# Sheet1.net
KiCad netlist of a schematic drawn in Altium Designer
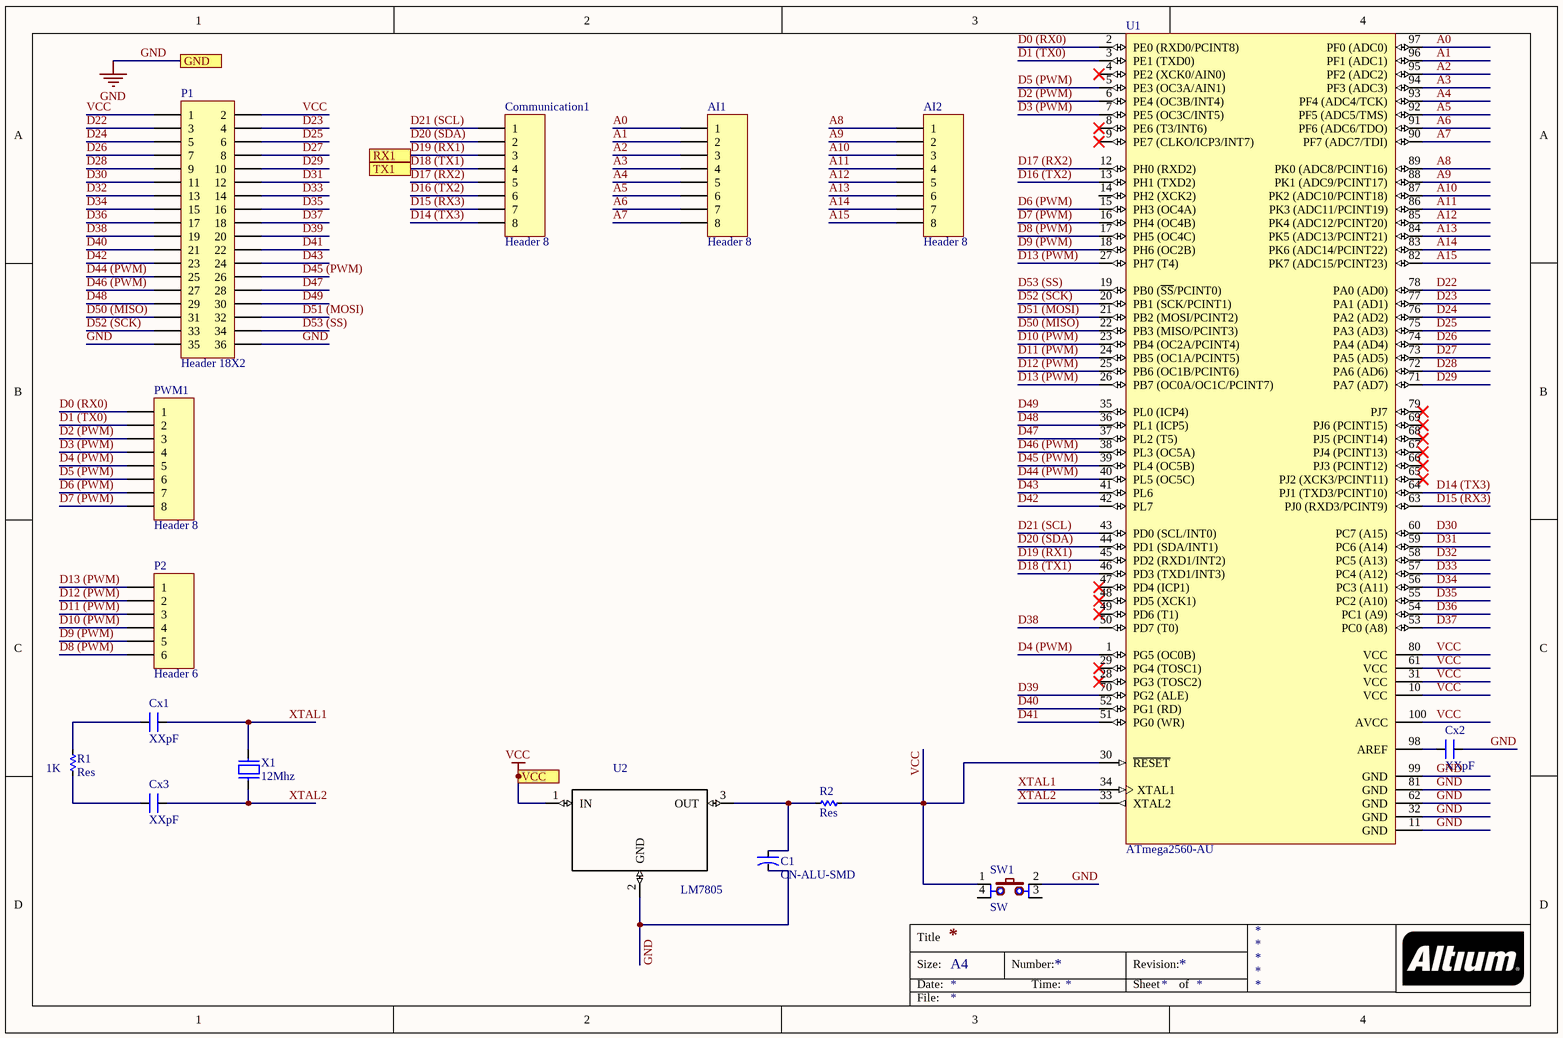
[diagram p0: Sheet1.SchDoc]

(export (version "E")
  (design (tool "Eeschema 10.0.6"))
  (components
    (comp (ref "AI1")
      (value "Header 8")
      (footprint "HDR1X8")
      (description "Header, 8-Pin")
      (fields (field (name "PUBLISHER") "Altium Limited"))
      (libsource (lib "Miscellaneous Connectors") (part "Header 8"))
    )
    (comp (ref "AI2")
      (value "Header 8")
      (footprint "HDR1X8")
      (description "Header, 8-Pin")
      (fields (field (name "PUBLISHER") "Altium Limited"))
      (libsource (lib "Miscellaneous Connectors") (part "Header 8"))
    )
    (comp (ref "C1")
      (value "CN-ALU-SMD")
      (footprint "CAP-ALU-SMD-4.5x5x1.4")
      (description "Polarized Capacitor (Axial)")
      (fields (field (name "PUBLISHER") "Altium Limited"))
      (libsource (lib "LIBRARY_altium mulinhkien") (part "CN-ALU-SMD"))
    )
    (comp (ref "Communication1")
      (value "Header 8")
      (footprint "HDR1X8")
      (description "Header, 8-Pin")
      (fields (field (name "PUBLISHER") "Altium Limited"))
      (libsource (lib "Miscellaneous Connectors") (part "Header 8"))
    )
    (comp (ref "Cx1")
      (value "XXpF")
      (footprint "CN-SMD-1206")
      (libsource (lib "LIBRARY_altium mulinhkien") (part "CN"))
    )
    (comp (ref "Cx2")
      (value "XXpF")
      (footprint "CN-SMD-1206")
      (libsource (lib "LIBRARY_altium mulinhkien") (part "CN"))
    )
    (comp (ref "Cx3")
      (value "XXpF")
      (footprint "CN-SMD-1206")
      (libsource (lib "LIBRARY_altium mulinhkien") (part "CN"))
    )
    (comp (ref "P1")
      (value "Header 18X2")
      (footprint "HDR2X18")
      (description "Header, 18-Pin, Dual row")
      (fields (field (name "PUBLISHER") "Altium Limited"))
      (libsource (lib "Miscellaneous Connectors") (part "Header 18X2"))
    )
    (comp (ref "P2")
      (value "Header 6")
      (footprint "HDR1X6")
      (description "Header, 6-Pin")
      (fields (field (name "PUBLISHER") "Altium Limited"))
      (libsource (lib "Miscellaneous Connectors") (part "Header 6"))
    )
    (comp (ref "PWM1")
      (value "Header 8")
      (footprint "HDR1X8")
      (description "Header, 8-Pin")
      (fields (field (name "PUBLISHER") "Altium Limited"))
      (libsource (lib "Miscellaneous Connectors") (part "Header 8"))
    )
    (comp (ref "R1")
      (value "Res")
      (footprint "RES-SMD-1206")
      (description "Resistor")
      (fields
        (field (name "MANUFACTURER") "Generic Components")
        (field (name "ALTIUM_VALUE") "1K")
        (field (name "PUBLISHER") "Altium Hobart Technology Centre")
      )
      (libsource (lib "LIBRARY_altium mulinhkien") (part "Res-SMD"))
    )
    (comp (ref "R2")
      (value "Res")
      (footprint "RES-SMD-1206")
      (description "Resistor")
      (fields
        (field (name "MANUFACTURER") "Generic Components")
        (field (name "PUBLISHER") "Altium Hobart Technology Centre")
      )
      (libsource (lib "LIBRARY_altium mulinhkien") (part "Res-SMD"))
    )
    (comp (ref "SW1")
      (value "SW")
      (footprint "SW2-DIP")
      (description "Switch button 4 pin")
      (libsource (lib "LIBRARY_altium mulinhkien") (part "SW4"))
    )
    (comp (ref "U1")
      (value "ATmega2560-AU")
      (footprint "TQFP100L")
      (libsource (lib "LIBRARY_altium mulinhkien") (part "ATmega2560-AU"))
    )
    (comp (ref "U2")
      (value "LM7805")
      (footprint "*TO220")
      (fields (field (name "MF") "Texas Instruments"))
      (libsource (lib "LM7805") (part "LM7805"))
    )
    (comp (ref "X1")
      (value "12Mhz")
      (footprint "XT2")
      (description "Crystal, 32.768 KHz, -40 to 85 degC, 3.2 x 1.5 x 0.9 mm SMD")
      (libsource (lib "LIBRARY_altium mulinhkien") (part "XT2"))
    )
  )
  (nets
    (net (code "1") (name "/A0") (class "Default")
      (node (ref "AI1") (pin "1") (pinfunction "1_1") (pintype "passive"))
      (node (ref "U1") (pin "97") (pinfunction "PF0_(ADC0)_97") (pintype "bidirectional"))
    )
    (net (code "2") (name "/A1") (class "Default")
      (node (ref "AI1") (pin "2") (pinfunction "2_2") (pintype "passive"))
      (node (ref "U1") (pin "96") (pinfunction "PF1_(ADC1)_96") (pintype "bidirectional"))
    )
    (net (code "3") (name "/A2") (class "Default")
      (node (ref "AI1") (pin "3") (pinfunction "3_3") (pintype "passive"))
      (node (ref "U1") (pin "95") (pinfunction "PF2_(ADC2)_95") (pintype "bidirectional"))
    )
    (net (code "4") (name "/A3") (class "Default")
      (node (ref "AI1") (pin "4") (pinfunction "4_4") (pintype "passive"))
      (node (ref "U1") (pin "94") (pinfunction "PF3_(ADC3)_94") (pintype "bidirectional"))
    )
    (net (code "5") (name "/A4") (class "Default")
      (node (ref "AI1") (pin "5") (pinfunction "5_5") (pintype "passive"))
      (node (ref "U1") (pin "93") (pinfunction "PF4_(ADC4/TCK)_93") (pintype "bidirectional"))
    )
    (net (code "6") (name "/A5") (class "Default")
      (node (ref "AI1") (pin "6") (pinfunction "6_6") (pintype "passive"))
      (node (ref "U1") (pin "92") (pinfunction "PF5_(ADC5/TMS)_92") (pintype "bidirectional"))
    )
    (net (code "7") (name "/A6") (class "Default")
      (node (ref "AI1") (pin "7") (pinfunction "7_7") (pintype "passive"))
      (node (ref "U1") (pin "91") (pinfunction "PF6_(ADC6/TDO)_91") (pintype "bidirectional"))
    )
    (net (code "8") (name "/A7") (class "Default")
      (node (ref "AI1") (pin "8") (pinfunction "8_8") (pintype "passive"))
      (node (ref "U1") (pin "90") (pinfunction "PF7_(ADC7/TDI)_90") (pintype "bidirectional"))
    )
    (net (code "9") (name "/A8") (class "Default")
      (node (ref "AI2") (pin "1") (pinfunction "1_1") (pintype "passive"))
      (node (ref "U1") (pin "89") (pinfunction "PK0_(ADC8/PCINT16)_89") (pintype "bidirectional"))
    )
    (net (code "10") (name "/A9") (class "Default")
      (node (ref "AI2") (pin "2") (pinfunction "2_2") (pintype "passive"))
      (node (ref "U1") (pin "88") (pinfunction "PK1_(ADC9/PCINT17)_88") (pintype "bidirectional"))
    )
    (net (code "11") (name "/A10") (class "Default")
      (node (ref "AI2") (pin "3") (pinfunction "3_3") (pintype "passive"))
      (node (ref "U1") (pin "87") (pinfunction "PK2_(ADC10/PCINT18)_87") (pintype "bidirectional"))
    )
    (net (code "12") (name "/A11") (class "Default")
      (node (ref "AI2") (pin "4") (pinfunction "4_4") (pintype "passive"))
      (node (ref "U1") (pin "86") (pinfunction "PK3_(ADC11/PCINT19)_86") (pintype "bidirectional"))
    )
    (net (code "13") (name "/A12") (class "Default")
      (node (ref "AI2") (pin "5") (pinfunction "5_5") (pintype "passive"))
      (node (ref "U1") (pin "85") (pinfunction "PK4_(ADC12/PCINT20)_85") (pintype "bidirectional"))
    )
    (net (code "14") (name "/A13") (class "Default")
      (node (ref "AI2") (pin "6") (pinfunction "6_6") (pintype "passive"))
      (node (ref "U1") (pin "84") (pinfunction "PK5_(ADC13/PCINT21)_84") (pintype "bidirectional"))
    )
    (net (code "15") (name "/A14") (class "Default")
      (node (ref "AI2") (pin "7") (pinfunction "7_7") (pintype "passive"))
      (node (ref "U1") (pin "83") (pinfunction "PK6_(ADC14/PCINT22)_83") (pintype "bidirectional"))
    )
    (net (code "16") (name "/A15") (class "Default")
      (node (ref "AI2") (pin "8") (pinfunction "8_8") (pintype "passive"))
      (node (ref "U1") (pin "82") (pinfunction "PK7_(ADC15/PCINT23)_82") (pintype "bidirectional"))
    )
    (net (code "17") (name "/D0 (RX0)") (class "Default")
      (node (ref "PWM1") (pin "1") (pinfunction "1_1") (pintype "passive"))
      (node (ref "U1") (pin "2") (pinfunction "PE0_(RXD0/PCINT8)_2") (pintype "bidirectional"))
    )
    (net (code "18") (name "/D1 (TX0)") (class "Default")
      (node (ref "PWM1") (pin "2") (pinfunction "2_2") (pintype "passive"))
      (node (ref "U1") (pin "3") (pinfunction "PE1_(TXD0)_3") (pintype "bidirectional"))
    )
    (net (code "19") (name "/D2 (PWM)") (class "Default")
      (node (ref "PWM1") (pin "3") (pinfunction "3_3") (pintype "passive"))
      (node (ref "U1") (pin "6") (pinfunction "PE4_(OC3B/INT4)_6") (pintype "bidirectional"))
    )
    (net (code "20") (name "/D3 (PWM)") (class "Default")
      (node (ref "PWM1") (pin "4") (pinfunction "4_4") (pintype "passive"))
      (node (ref "U1") (pin "7") (pinfunction "PE5_(OC3C/INT5)_7") (pintype "bidirectional"))
    )
    (net (code "21") (name "/D4 (PWM)") (class "Default")
      (node (ref "PWM1") (pin "5") (pinfunction "5_5") (pintype "passive"))
      (node (ref "U1") (pin "1") (pinfunction "PG5_(OC0B)_1") (pintype "bidirectional"))
    )
    (net (code "22") (name "/D5 (PWM)") (class "Default")
      (node (ref "PWM1") (pin "6") (pinfunction "6_6") (pintype "passive"))
      (node (ref "U1") (pin "5") (pinfunction "PE3_(OC3A/AIN1)_5") (pintype "bidirectional"))
    )
    (net (code "23") (name "/D6 (PWM)") (class "Default")
      (node (ref "PWM1") (pin "7") (pinfunction "7_7") (pintype "passive"))
      (node (ref "U1") (pin "15") (pinfunction "PH3_(OC4A)_15") (pintype "bidirectional"))
    )
    (net (code "24") (name "/D7 (PWM)") (class "Default")
      (node (ref "PWM1") (pin "8") (pinfunction "8_8") (pintype "passive"))
      (node (ref "U1") (pin "16") (pinfunction "PH4_(OC4B)_16") (pintype "bidirectional"))
    )
    (net (code "25") (name "/D8 (PWM)") (class "Default")
      (node (ref "P2") (pin "6") (pinfunction "6_6") (pintype "passive"))
      (node (ref "U1") (pin "17") (pinfunction "PH5_(OC4C)_17") (pintype "bidirectional"))
    )
    (net (code "26") (name "/D9 (PWM)") (class "Default")
      (node (ref "P2") (pin "5") (pinfunction "5_5") (pintype "passive"))
      (node (ref "U1") (pin "18") (pinfunction "PH6_(OC2B)_18") (pintype "bidirectional"))
    )
    (net (code "27") (name "/D10 (PWM)") (class "Default")
      (node (ref "P2") (pin "4") (pinfunction "4_4") (pintype "passive"))
      (node (ref "U1") (pin "23") (pinfunction "PB4_(OC2A/PCINT4)_23") (pintype "bidirectional"))
    )
    (net (code "28") (name "/D11 (PWM)") (class "Default")
      (node (ref "P2") (pin "3") (pinfunction "3_3") (pintype "passive"))
      (node (ref "U1") (pin "24") (pinfunction "PB5_(OC1A/PCINT5)_24") (pintype "bidirectional"))
    )
    (net (code "29") (name "/D12 (PWM)") (class "Default")
      (node (ref "P2") (pin "2") (pinfunction "2_2") (pintype "passive"))
      (node (ref "U1") (pin "25") (pinfunction "PB6_(OC1B/PCINT6)_25") (pintype "bidirectional"))
    )
    (net (code "30") (name "/D13 (PWM)") (class "Default")
      (node (ref "P2") (pin "1") (pinfunction "1_1") (pintype "passive"))
      (node (ref "U1") (pin "26") (pinfunction "PB7_(OC0A/OC1C/PCINT7)_26") (pintype "bidirectional"))
      (node (ref "U1") (pin "27") (pinfunction "PH7_(T4)_27") (pintype "bidirectional"))
    )
    (net (code "31") (name "/D14 (TX3)") (class "Default")
      (node (ref "Communication1") (pin "8") (pinfunction "8_8") (pintype "passive"))
      (node (ref "U1") (pin "64") (pinfunction "PJ1_(TXD3/PCINT10)_64") (pintype "bidirectional"))
    )
    (net (code "32") (name "/D15 (RX3)") (class "Default")
      (node (ref "Communication1") (pin "7") (pinfunction "7_7") (pintype "passive"))
      (node (ref "U1") (pin "63") (pinfunction "PJ0_(RXD3/PCINT9)_63") (pintype "bidirectional"))
    )
    (net (code "33") (name "/D16 (TX2)") (class "Default")
      (node (ref "Communication1") (pin "6") (pinfunction "6_6") (pintype "passive"))
      (node (ref "U1") (pin "13") (pinfunction "PH1_(TXD2)_13") (pintype "bidirectional"))
    )
    (net (code "34") (name "/D17 (RX2)") (class "Default")
      (node (ref "Communication1") (pin "5") (pinfunction "5_5") (pintype "passive"))
      (node (ref "U1") (pin "12") (pinfunction "PH0_(RXD2)_12") (pintype "bidirectional"))
    )
    (net (code "35") (name "/D18 (TX1)") (class "Default")
      (node (ref "Communication1") (pin "4") (pinfunction "4_4") (pintype "passive"))
      (node (ref "U1") (pin "46") (pinfunction "PD3_(TXD1/INT3)_46") (pintype "bidirectional"))
    )
    (net (code "36") (name "/D19 (RX1)") (class "Default")
      (node (ref "Communication1") (pin "3") (pinfunction "3_3") (pintype "passive"))
      (node (ref "U1") (pin "45") (pinfunction "PD2_(RXD1/INT2)_45") (pintype "bidirectional"))
    )
    (net (code "37") (name "/D20 (SDA)") (class "Default")
      (node (ref "Communication1") (pin "2") (pinfunction "2_2") (pintype "passive"))
      (node (ref "U1") (pin "44") (pinfunction "PD1_(SDA/INT1)_44") (pintype "bidirectional"))
    )
    (net (code "38") (name "/D21 (SCL)") (class "Default")
      (node (ref "Communication1") (pin "1") (pinfunction "1_1") (pintype "passive"))
      (node (ref "U1") (pin "43") (pinfunction "PD0_(SCL/INT0)_43") (pintype "bidirectional"))
    )
    (net (code "39") (name "/D22") (class "Default")
      (node (ref "P1") (pin "3") (pinfunction "3_3") (pintype "passive"))
      (node (ref "U1") (pin "78") (pinfunction "PA0_(AD0)_78") (pintype "bidirectional"))
    )
    (net (code "40") (name "/D23") (class "Default")
      (node (ref "P1") (pin "4") (pinfunction "4_4") (pintype "passive"))
      (node (ref "U1") (pin "77") (pinfunction "PA1_(AD1)_77") (pintype "bidirectional"))
    )
    (net (code "41") (name "/D24") (class "Default")
      (node (ref "P1") (pin "5") (pinfunction "5_5") (pintype "passive"))
      (node (ref "U1") (pin "76") (pinfunction "PA2_(AD2)_76") (pintype "bidirectional"))
    )
    (net (code "42") (name "/D25") (class "Default")
      (node (ref "P1") (pin "6") (pinfunction "6_6") (pintype "passive"))
      (node (ref "U1") (pin "75") (pinfunction "PA3_(AD3)_75") (pintype "bidirectional"))
    )
    (net (code "43") (name "/D26") (class "Default")
      (node (ref "P1") (pin "7") (pinfunction "7_7") (pintype "passive"))
      (node (ref "U1") (pin "74") (pinfunction "PA4_(AD4)_74") (pintype "bidirectional"))
    )
    (net (code "44") (name "/D27") (class "Default")
      (node (ref "P1") (pin "8") (pinfunction "8_8") (pintype "passive"))
      (node (ref "U1") (pin "73") (pinfunction "PA5_(AD5)_73") (pintype "bidirectional"))
    )
    (net (code "45") (name "/D28") (class "Default")
      (node (ref "P1") (pin "9") (pinfunction "9_9") (pintype "passive"))
      (node (ref "U1") (pin "72") (pinfunction "PA6_(AD6)_72") (pintype "bidirectional"))
    )
    (net (code "46") (name "/D29") (class "Default")
      (node (ref "P1") (pin "10") (pinfunction "10_10") (pintype "passive"))
      (node (ref "U1") (pin "71") (pinfunction "PA7_(AD7)_71") (pintype "bidirectional"))
    )
    (net (code "47") (name "/D30") (class "Default")
      (node (ref "P1") (pin "11") (pinfunction "11_11") (pintype "passive"))
      (node (ref "U1") (pin "60") (pinfunction "PC7_(A15)_60") (pintype "bidirectional"))
    )
    (net (code "48") (name "/D31") (class "Default")
      (node (ref "P1") (pin "12") (pinfunction "12_12") (pintype "passive"))
      (node (ref "U1") (pin "59") (pinfunction "PC6_(A14)_59") (pintype "bidirectional"))
    )
    (net (code "49") (name "/D32") (class "Default")
      (node (ref "P1") (pin "13") (pinfunction "13_13") (pintype "passive"))
      (node (ref "U1") (pin "58") (pinfunction "PC5_(A13)_58") (pintype "bidirectional"))
    )
    (net (code "50") (name "/D33") (class "Default")
      (node (ref "P1") (pin "14") (pinfunction "14_14") (pintype "passive"))
      (node (ref "U1") (pin "57") (pinfunction "PC4_(A12)_57") (pintype "bidirectional"))
    )
    (net (code "51") (name "/D34") (class "Default")
      (node (ref "P1") (pin "15") (pinfunction "15_15") (pintype "passive"))
      (node (ref "U1") (pin "56") (pinfunction "PC3_(A11)_56") (pintype "bidirectional"))
    )
    (net (code "52") (name "/D35") (class "Default")
      (node (ref "P1") (pin "16") (pinfunction "16_16") (pintype "passive"))
      (node (ref "U1") (pin "55") (pinfunction "PC2_(A10)_55") (pintype "bidirectional"))
    )
    (net (code "53") (name "/D36") (class "Default")
      (node (ref "P1") (pin "17") (pinfunction "17_17") (pintype "passive"))
      (node (ref "U1") (pin "54") (pinfunction "PC1_(A9)_54") (pintype "bidirectional"))
    )
    (net (code "54") (name "/D37") (class "Default")
      (node (ref "P1") (pin "18") (pinfunction "18_18") (pintype "passive"))
      (node (ref "U1") (pin "53") (pinfunction "PC0_(A8)_53") (pintype "bidirectional"))
    )
    (net (code "55") (name "/D38") (class "Default")
      (node (ref "P1") (pin "19") (pinfunction "19_19") (pintype "passive"))
      (node (ref "U1") (pin "50") (pinfunction "PD7_(T0)_50") (pintype "bidirectional"))
    )
    (net (code "56") (name "/D39") (class "Default")
      (node (ref "P1") (pin "20") (pinfunction "20_20") (pintype "passive"))
      (node (ref "U1") (pin "70") (pinfunction "PG2_(ALE)_70") (pintype "bidirectional"))
    )
    (net (code "57") (name "/D40") (class "Default")
      (node (ref "P1") (pin "21") (pinfunction "21_21") (pintype "passive"))
      (node (ref "U1") (pin "52") (pinfunction "PG1_(RD)_52") (pintype "bidirectional"))
    )
    (net (code "58") (name "/D41") (class "Default")
      (node (ref "P1") (pin "22") (pinfunction "22_22") (pintype "passive"))
      (node (ref "U1") (pin "51") (pinfunction "PG0_(WR)_51") (pintype "bidirectional"))
    )
    (net (code "59") (name "/D42") (class "Default")
      (node (ref "P1") (pin "23") (pinfunction "23_23") (pintype "passive"))
      (node (ref "U1") (pin "42") (pinfunction "PL7_42") (pintype "bidirectional"))
    )
    (net (code "60") (name "/D43") (class "Default")
      (node (ref "P1") (pin "24") (pinfunction "24_24") (pintype "passive"))
      (node (ref "U1") (pin "41") (pinfunction "PL6_41") (pintype "bidirectional"))
    )
    (net (code "61") (name "/D44 (PWM)") (class "Default")
      (node (ref "P1") (pin "25") (pinfunction "25_25") (pintype "passive"))
      (node (ref "U1") (pin "40") (pinfunction "PL5_(OC5C)_40") (pintype "bidirectional"))
    )
    (net (code "62") (name "/D45 (PWM)") (class "Default")
      (node (ref "P1") (pin "26") (pinfunction "26_26") (pintype "passive"))
      (node (ref "U1") (pin "39") (pinfunction "PL4_(OC5B)_39") (pintype "bidirectional"))
    )
    (net (code "63") (name "/D46 (PWM)") (class "Default")
      (node (ref "P1") (pin "27") (pinfunction "27_27") (pintype "passive"))
      (node (ref "U1") (pin "38") (pinfunction "PL3_(OC5A)_38") (pintype "bidirectional"))
    )
    (net (code "64") (name "/D47") (class "Default")
      (node (ref "P1") (pin "28") (pinfunction "28_28") (pintype "passive"))
      (node (ref "U1") (pin "37") (pinfunction "PL2_(T5)_37") (pintype "bidirectional"))
    )
    (net (code "65") (name "/D48") (class "Default")
      (node (ref "P1") (pin "29") (pinfunction "29_29") (pintype "passive"))
      (node (ref "U1") (pin "36") (pinfunction "PL1_(ICP5)_36") (pintype "bidirectional"))
    )
    (net (code "66") (name "/D49") (class "Default")
      (node (ref "P1") (pin "30") (pinfunction "30_30") (pintype "passive"))
      (node (ref "U1") (pin "35") (pinfunction "PL0_(ICP4)_35") (pintype "bidirectional"))
    )
    (net (code "67") (name "/D50 (MISO)") (class "Default")
      (node (ref "P1") (pin "31") (pinfunction "31_31") (pintype "passive"))
      (node (ref "U1") (pin "22") (pinfunction "PB3_(MISO/PCINT3)_22") (pintype "bidirectional"))
    )
    (net (code "68") (name "/D51 (MOSI)") (class "Default")
      (node (ref "P1") (pin "32") (pinfunction "32_32") (pintype "passive"))
      (node (ref "U1") (pin "21") (pinfunction "PB2_(MOSI/PCINT2)_21") (pintype "bidirectional"))
    )
    (net (code "69") (name "/D52 (SCK)") (class "Default")
      (node (ref "P1") (pin "33") (pinfunction "33_33") (pintype "passive"))
      (node (ref "U1") (pin "20") (pinfunction "PB1_(SCK/PCINT1)_20") (pintype "bidirectional"))
    )
    (net (code "70") (name "/D53 (SS)") (class "Default")
      (node (ref "P1") (pin "34") (pinfunction "34_34") (pintype "passive"))
      (node (ref "U1") (pin "19") (pinfunction "PB0_(~{SS}/PCINT0)_19") (pintype "bidirectional"))
    )
    (net (code "71") (name "/XTAL1") (class "Default")
      (node (ref "Cx1") (pin "2") (pinfunction "2_2") (pintype "passive"))
      (node (ref "U1") (pin "34") (pinfunction "XTAL1_34") (pintype "input"))
      (node (ref "X1") (pin "2") (pinfunction "2_2") (pintype "passive"))
    )
    (net (code "72") (name "/XTAL2") (class "Default")
      (node (ref "Cx3") (pin "2") (pinfunction "2_2") (pintype "passive"))
      (node (ref "U1") (pin "33") (pinfunction "XTAL2_33") (pintype "output"))
      (node (ref "X1") (pin "1") (pinfunction "1_1") (pintype "passive"))
    )
    (net (code "73") (name "GND") (class "Default")
      (node (ref "C1") (pin "2") (pinfunction "2_2") (pintype "passive"))
      (node (ref "Cx2") (pin "2") (pinfunction "2_2") (pintype "passive"))
      (node (ref "P1") (pin "35") (pinfunction "35_35") (pintype "passive"))
      (node (ref "P1") (pin "36") (pinfunction "36_36") (pintype "passive"))
      (node (ref "SW1") (pin "2") (pinfunction "2_2") (pintype "passive"))
      (node (ref "U1") (pin "11") (pinfunction "GND_11") (pintype "power_in"))
      (node (ref "U1") (pin "32") (pinfunction "GND_32") (pintype "power_in"))
      (node (ref "U1") (pin "62") (pinfunction "GND_62") (pintype "power_in"))
      (node (ref "U1") (pin "81") (pinfunction "GND_81") (pintype "power_in"))
      (node (ref "U1") (pin "99") (pinfunction "GND_99") (pintype "power_in"))
      (node (ref "U2") (pin "2") (pinfunction "GND_2") (pintype "bidirectional"))
    )
    (net (code "74") (name "Net-(Cx1-Pad1)") (class "Default")
      (node (ref "Cx1") (pin "1") (pinfunction "1_1") (pintype "passive"))
      (node (ref "R1") (pin "1") (pinfunction "1_1") (pintype "passive"))
    )
    (net (code "75") (name "Net-(Cx3-Pad1)") (class "Default")
      (node (ref "Cx3") (pin "1") (pinfunction "1_1") (pintype "passive"))
      (node (ref "R1") (pin "2") (pinfunction "2_2") (pintype "passive"))
    )
    (net (code "76") (name "Net-(U1-AREF)") (class "Default")
      (node (ref "Cx2") (pin "1") (pinfunction "1_1") (pintype "passive"))
      (node (ref "U1") (pin "98") (pinfunction "AREF_98") (pintype "power_in"))
    )
    (net (code "77") (name "Net-(U2-OUT)") (class "Default")
      (node (ref "C1") (pin "1") (pinfunction "1_1") (pintype "passive"))
      (node (ref "R2") (pin "2") (pinfunction "2_2") (pintype "passive"))
      (node (ref "U2") (pin "3") (pinfunction "OUT_3") (pintype "bidirectional"))
    )
    (net (code "78") (name "VCC") (class "Default")
      (node (ref "P1") (pin "1") (pinfunction "1_1") (pintype "passive"))
      (node (ref "P1") (pin "2") (pinfunction "2_2") (pintype "passive"))
      (node (ref "R2") (pin "1") (pinfunction "1_1") (pintype "passive"))
      (node (ref "SW1") (pin "1") (pintype "passive"))
      (node (ref "U1") (pin "10") (pinfunction "VCC_10") (pintype "power_in"))
      (node (ref "U1") (pin "100") (pinfunction "AVCC_100") (pintype "power_in"))
      (node (ref "U1") (pin "30") (pinfunction "~{RESET}_30") (pintype "input"))
      (node (ref "U1") (pin "31") (pinfunction "VCC_31") (pintype "power_in"))
      (node (ref "U1") (pin "61") (pinfunction "VCC_61") (pintype "power_in"))
      (node (ref "U1") (pin "80") (pinfunction "VCC_80") (pintype "power_in"))
      (node (ref "U2") (pin "1") (pinfunction "IN_1") (pintype "bidirectional"))
    )
    (net (code "79") (name "unconnected-(SW1-Pad3)") (class "Default")
      (node (ref "SW1") (pin "3") (pinfunction "3_3") (pintype "passive"))
    )
    (net (code "80") (name "unconnected-(SW1-Pad4)") (class "Default")
      (node (ref "SW1") (pin "4") (pinfunction "4_4") (pintype "passive"))
    )
    (net (code "81") (name "unconnected-(U1-PD4_(ICP1)-Pad47)") (class "Default")
      (node (ref "U1") (pin "47") (pinfunction "PD4_(ICP1)_47") (pintype "bidirectional+no_connect"))
    )
    (net (code "82") (name "unconnected-(U1-PD5_(XCK1)-Pad48)") (class "Default")
      (node (ref "U1") (pin "48") (pinfunction "PD5_(XCK1)_48") (pintype "bidirectional+no_connect"))
    )
    (net (code "83") (name "unconnected-(U1-PD6_(T1)-Pad49)") (class "Default")
      (node (ref "U1") (pin "49") (pinfunction "PD6_(T1)_49") (pintype "bidirectional+no_connect"))
    )
    (net (code "84") (name "unconnected-(U1-PE2_(XCK0{slash}AIN0)-Pad4)") (class "Default")
      (node (ref "U1") (pin "4") (pinfunction "PE2_(XCK0/AIN0)_4") (pintype "bidirectional+no_connect"))
    )
    (net (code "85") (name "unconnected-(U1-PE6_(T3{slash}INT6)-Pad8)") (class "Default")
      (node (ref "U1") (pin "8") (pinfunction "PE6_(T3/INT6)_8") (pintype "bidirectional+no_connect"))
    )
    (net (code "86") (name "unconnected-(U1-PE7_(CLKO{slash}ICP3{slash}INT7)-Pad9)") (class "Default")
      (node (ref "U1") (pin "9") (pinfunction "PE7_(CLKO/ICP3/INT7)_9") (pintype "bidirectional+no_connect"))
    )
    (net (code "87") (name "unconnected-(U1-PG3_(TOSC2)-Pad28)") (class "Default")
      (node (ref "U1") (pin "28") (pinfunction "PG3_(TOSC2)_28") (pintype "bidirectional+no_connect"))
    )
    (net (code "88") (name "unconnected-(U1-PG4_(TOSC1)-Pad29)") (class "Default")
      (node (ref "U1") (pin "29") (pinfunction "PG4_(TOSC1)_29") (pintype "bidirectional+no_connect"))
    )
    (net (code "89") (name "unconnected-(U1-PH2_(XCK2)-Pad14)") (class "Default")
      (node (ref "U1") (pin "14") (pinfunction "PH2_(XCK2)_14") (pintype "bidirectional"))
    )
    (net (code "90") (name "unconnected-(U1-PJ2_(XCK3{slash}PCINT11)-Pad65)") (class "Default")
      (node (ref "U1") (pin "65") (pinfunction "PJ2_(XCK3/PCINT11)_65") (pintype "bidirectional+no_connect"))
    )
    (net (code "91") (name "unconnected-(U1-PJ3_(PCINT12)-Pad66)") (class "Default")
      (node (ref "U1") (pin "66") (pinfunction "PJ3_(PCINT12)_66") (pintype "bidirectional+no_connect"))
    )
    (net (code "92") (name "unconnected-(U1-PJ4_(PCINT13)-Pad67)") (class "Default")
      (node (ref "U1") (pin "67") (pinfunction "PJ4_(PCINT13)_67") (pintype "bidirectional+no_connect"))
    )
    (net (code "93") (name "unconnected-(U1-PJ5_(PCINT14)-Pad68)") (class "Default")
      (node (ref "U1") (pin "68") (pinfunction "PJ5_(PCINT14)_68") (pintype "bidirectional+no_connect"))
    )
    (net (code "94") (name "unconnected-(U1-PJ6_(PCINT15)-Pad69)") (class "Default")
      (node (ref "U1") (pin "69") (pinfunction "PJ6_(PCINT15)_69") (pintype "bidirectional+no_connect"))
    )
    (net (code "95") (name "unconnected-(U1-PJ7-Pad79)") (class "Default")
      (node (ref "U1") (pin "79") (pinfunction "PJ7_79") (pintype "bidirectional+no_connect"))
    )
  )
)
